# STM32_2024-08-02.net
KiCad netlist of a schematic drawn in EasyEDA Pro
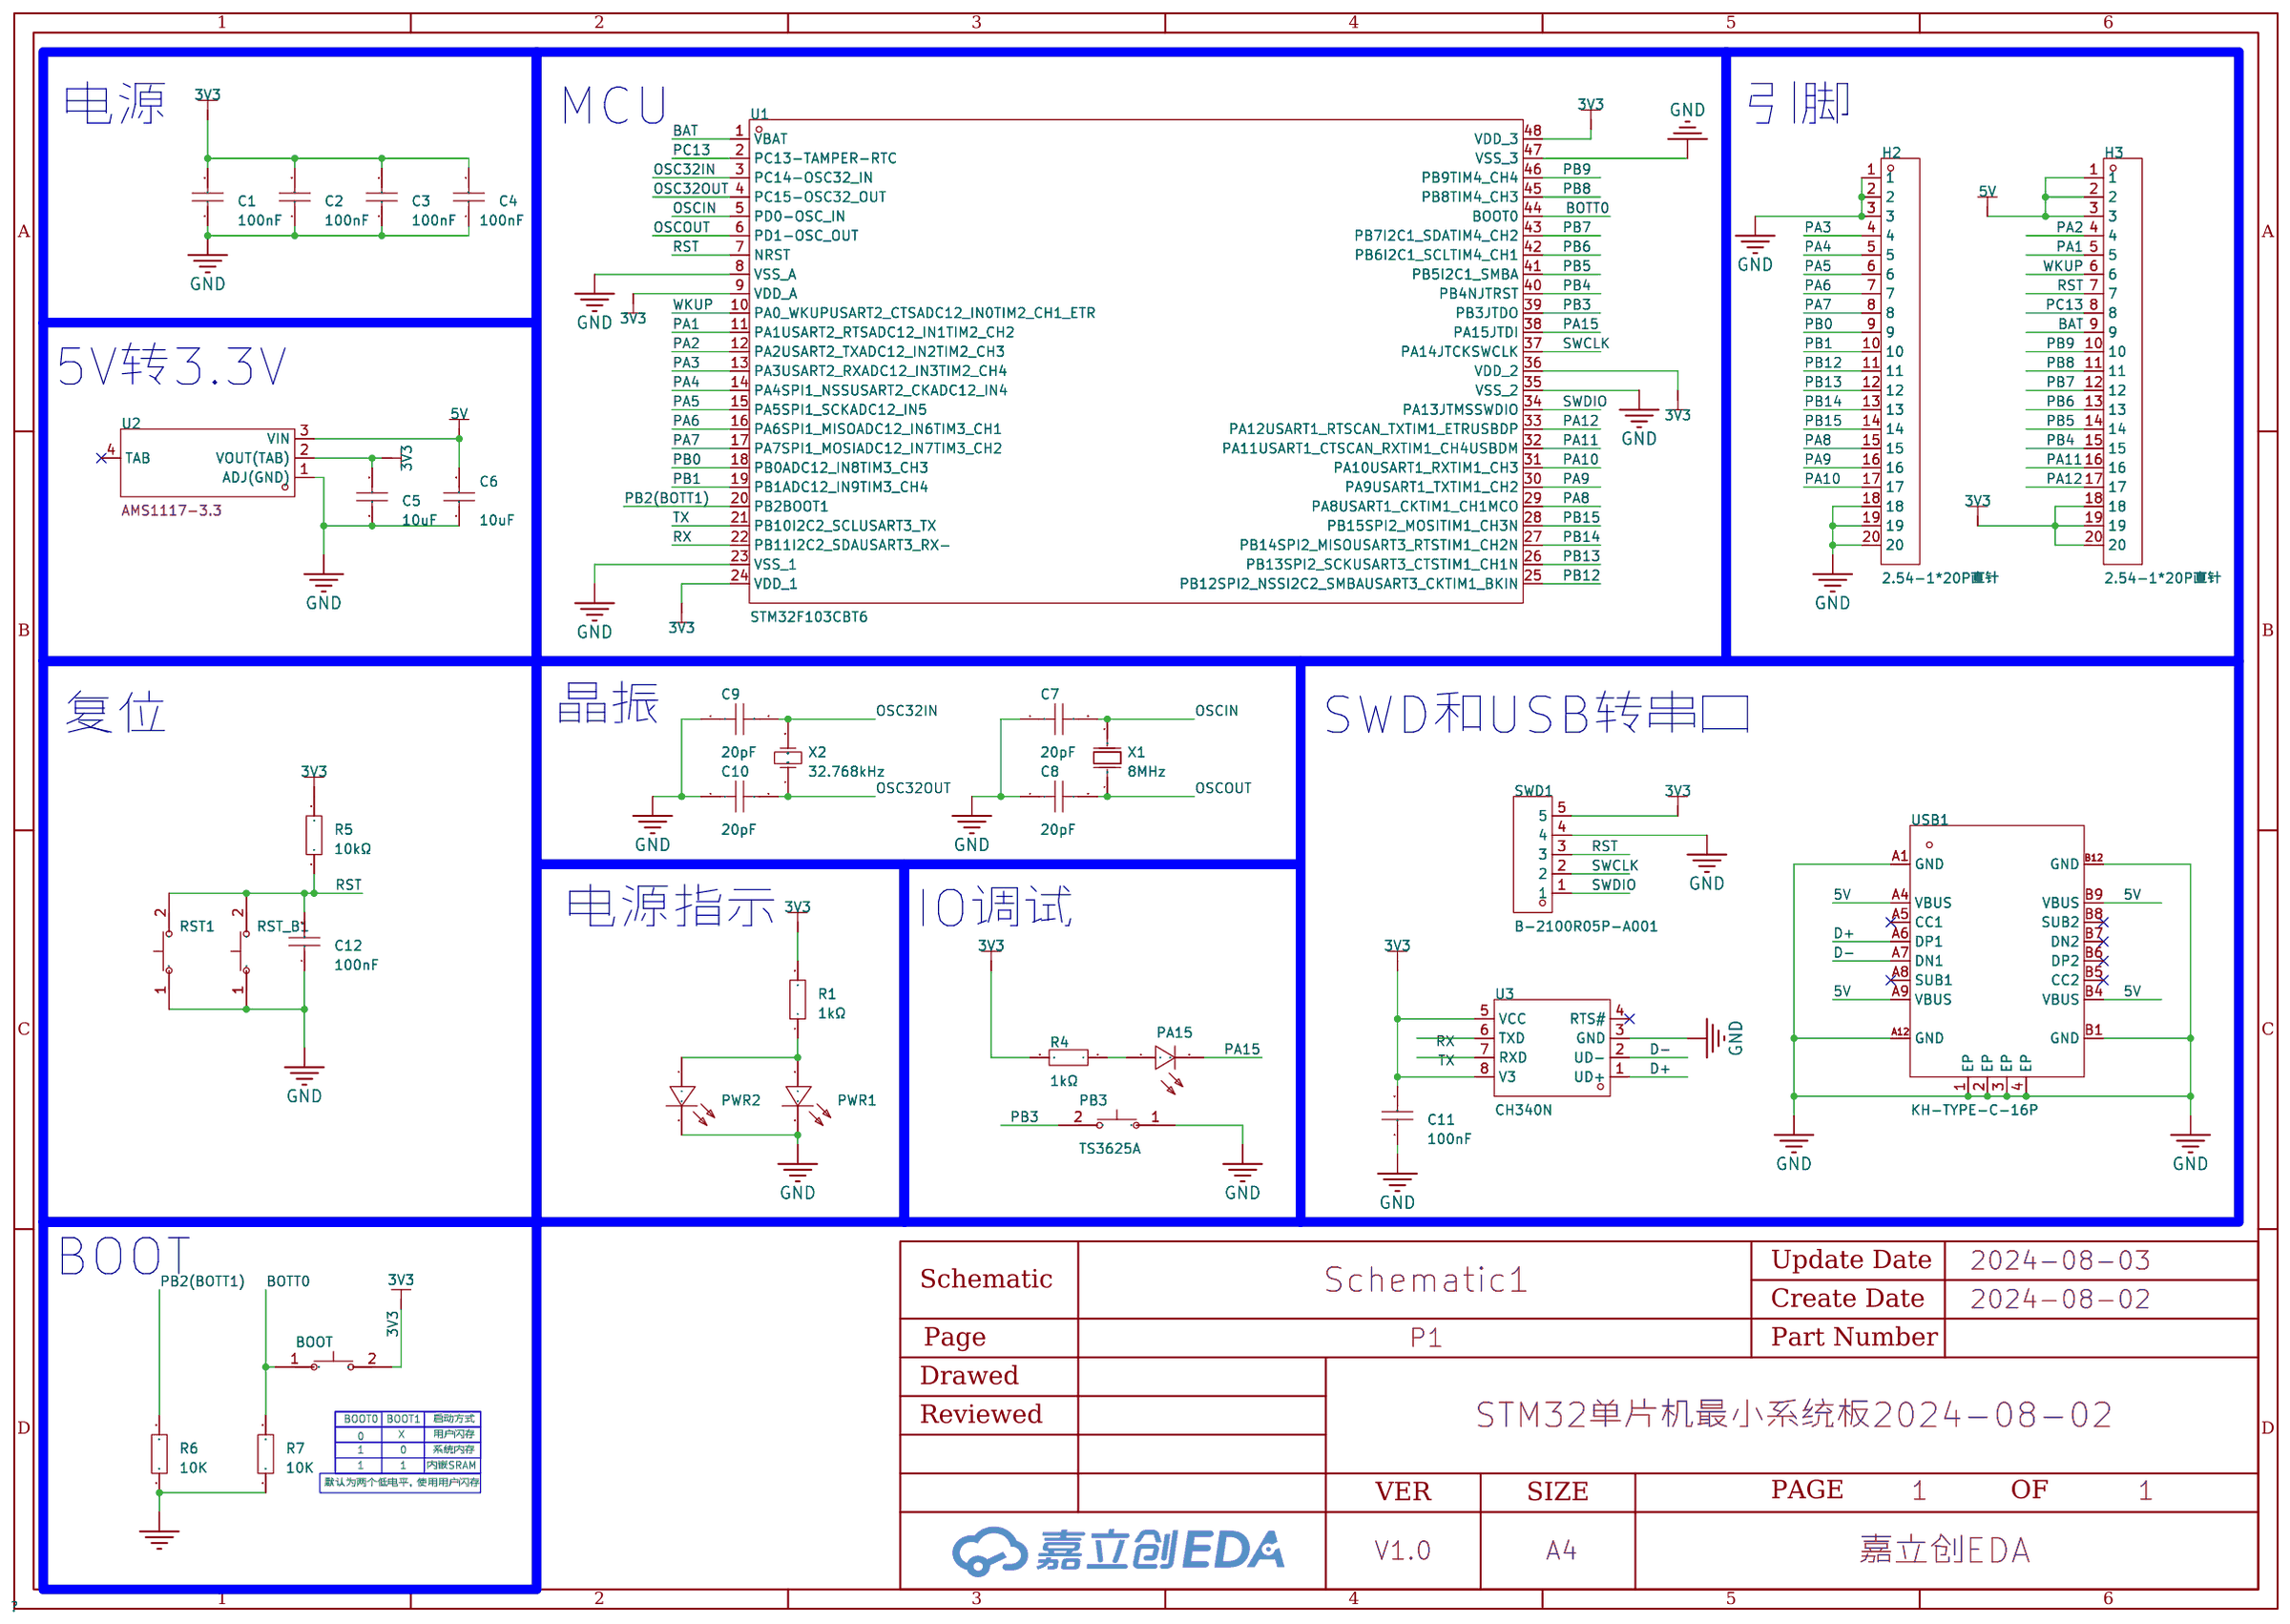
[diagram p0: schematic sheet]

(export (version "E")
  (design (tool "Eeschema 10.0.6"))
  (components
    (comp (ref "BOOT")
      (value "TS3625A")
      (footprint "easyedapro:KEY-SMD_L6.0-W3.5-LS8.4")
      (fields (field (name "Manufacturer") "SHOU HAN(首韩)"))
      (libsource (lib "easyedapro") (part "TS3625A"))
    )
    (comp (ref "C1")
      (value "100nF")
      (footprint "easyedapro:C0805")
      (description "温度系数:X7R;容值:100nF;精度:±10%;额定电压:50V;")
      (fields (field (name "Manufacturer Part") "0805B104K500NT") (field (name "Manufacturer") "FH(风华)"))
      (libsource (lib "easyedapro") (part "0805B104K500NT"))
    )
    (comp (ref "C2")
      (value "100nF")
      (footprint "easyedapro:C0805")
      (description "温度系数:X7R;容值:100nF;精度:±10%;额定电压:50V;")
      (fields (field (name "Manufacturer Part") "0805B104K500NT") (field (name "Manufacturer") "FH(风华)"))
      (libsource (lib "easyedapro") (part "0805B104K500NT"))
    )
    (comp (ref "C3")
      (value "100nF")
      (footprint "easyedapro:C0805")
      (description "温度系数:X7R;容值:100nF;精度:±10%;额定电压:50V;")
      (fields (field (name "Manufacturer Part") "0805B104K500NT") (field (name "Manufacturer") "FH(风华)"))
      (libsource (lib "easyedapro") (part "0805B104K500NT"))
    )
    (comp (ref "C4")
      (value "100nF")
      (footprint "easyedapro:C0805")
      (description "温度系数:X7R;容值:100nF;精度:±10%;额定电压:50V;")
      (fields (field (name "Manufacturer Part") "0805B104K500NT") (field (name "Manufacturer") "FH(风华)"))
      (libsource (lib "easyedapro") (part "0805B104K500NT"))
    )
    (comp (ref "C5")
      (value "10uF")
      (footprint "easyedapro:C0805")
      (description "容值:10uF;精度:±10%;额定电压:25V;材质(温度系数):X5R;")
      (fields (field (name "Manufacturer Part") "0805X106K250NT") (field (name "Manufacturer") "FH(风华)"))
      (libsource (lib "easyedapro") (part "0805X106K250NT"))
    )
    (comp (ref "C6")
      (value "10uF")
      (footprint "easyedapro:C0805")
      (description "容值:10uF;精度:±10%;额定电压:25V;材质(温度系数):X5R;")
      (fields (field (name "Manufacturer Part") "0805X106K250NT") (field (name "Manufacturer") "FH(风华)"))
      (libsource (lib "easyedapro") (part "0805X106K250NT"))
    )
    (comp (ref "C7")
      (value "20pF")
      (footprint "easyedapro:C0805")
      (description "容值:20pF;精度:±5%;额定电压:50V;材质(温度系数):C0G;")
      (fields (field (name "Manufacturer Part") "0805CG200J500NT") (field (name "Manufacturer") "FH(风华)"))
      (libsource (lib "easyedapro") (part "0805CG200J500NT"))
    )
    (comp (ref "C8")
      (value "20pF")
      (footprint "easyedapro:C0805")
      (description "容值:20pF;精度:±5%;额定电压:50V;材质(温度系数):C0G;")
      (fields (field (name "Manufacturer Part") "0805CG200J500NT") (field (name "Manufacturer") "FH(风华)"))
      (libsource (lib "easyedapro") (part "0805CG200J500NT"))
    )
    (comp (ref "C9")
      (value "20pF")
      (footprint "easyedapro:C0805")
      (description "容值:20pF;精度:±5%;额定电压:50V;材质(温度系数):C0G;")
      (fields (field (name "Manufacturer Part") "0805CG200J500NT") (field (name "Manufacturer") "FH(风华)"))
      (libsource (lib "easyedapro") (part "0805CG200J500NT"))
    )
    (comp (ref "C10")
      (value "20pF")
      (footprint "easyedapro:C0805")
      (description "容值:20pF;精度:±5%;额定电压:50V;材质(温度系数):C0G;")
      (fields (field (name "Manufacturer Part") "0805CG200J500NT") (field (name "Manufacturer") "FH(风华)"))
      (libsource (lib "easyedapro") (part "0805CG200J500NT"))
    )
    (comp (ref "C11")
      (value "100nF")
      (footprint "easyedapro:C0805")
      (description "温度系数:X7R;容值:100nF;精度:±10%;额定电压:50V;")
      (fields (field (name "Manufacturer Part") "0805B104K500NT") (field (name "Manufacturer") "FH(风华)"))
      (libsource (lib "easyedapro") (part "0805B104K500NT"))
    )
    (comp (ref "C12")
      (value "100nF")
      (footprint "easyedapro:C0805")
      (description "温度系数:X7R;容值:100nF;精度:±10%;额定电压:50V;")
      (fields (field (name "Manufacturer Part") "0805B104K500NT") (field (name "Manufacturer") "FH(风华)"))
      (libsource (lib "easyedapro") (part "0805B104K500NT"))
    )
    (comp (ref "H2")
      (value "2.54-1*20P直针")
      (footprint "easyedapro:HDR-TH_20P-P2.54-V-M-1")
      (fields (field (name "Manufacturer") "BOOMELE(博穆精密)"))
      (libsource (lib "easyedapro") (part "Header-Male-2.54_1x20"))
    )
    (comp (ref "H3")
      (value "2.54-1*20P直针")
      (footprint "easyedapro:HDR-TH_20P-P2.54-V-M-1")
      (fields (field (name "Manufacturer") "BOOMELE(博穆精密)"))
      (libsource (lib "easyedapro") (part "Header-Male-2.54_1x20"))
    )
    (comp (ref "PA15")
      (value "NCD0805G1")
      (footprint "easyedapro:LED0805-R-RD")
      (description "发光颜色:翠绿;")
      (fields (field (name "Manufacturer") "国星光电"))
      (libsource (lib "easyedapro") (part "17-21SURC/S530-A3/TR8"))
    )
    (comp (ref "PB3")
      (value "TS3625A")
      (footprint "easyedapro:KEY-SMD_L6.0-W3.5-LS8.4")
      (fields (field (name "Manufacturer") "SHOU HAN(首韩)"))
      (libsource (lib "easyedapro") (part "TS3625A"))
    )
    (comp (ref "PWR1")
      (value "NCD0805G1")
      (footprint "easyedapro:LED0805-R-RD")
      (description "照明颜色:翠绿;色温 - CCT（K）:-;主波长/色坐标:525~537.5nm;")
      (fields (field (name "Manufacturer") "国星光电"))
      (libsource (lib "easyedapro") (part "FC-2012UGK-520D5"))
    )
    (comp (ref "PWR2")
      (value "NCD0805G1")
      (footprint "easyedapro:LED0805-R-RD")
      (description "照明颜色:翠绿;色温 - CCT（K）:-;主波长/色坐标:525~537.5nm;")
      (fields (field (name "Manufacturer") "国星光电"))
      (libsource (lib "easyedapro") (part "FC-2012UGK-520D5"))
    )
    (comp (ref "R1")
      (value "1kΩ")
      (footprint "easyedapro:R0805")
      (description "精度:±1%;功率:125mW;电阻类型:厚膜电阻;最大工作电压:150V;温度系数:±100ppm/°C;工作温度范围:-55°C~+155°C;阻值:1kΩ;")
      (fields
        (field (name "Manufacturer Part") "0805W8F1001T5E")
        (field (name "Manufacturer") "UNI-ROYAL(厚声)")
      )
      (libsource (lib "easyedapro") (part "0805W8F1001T5E"))
    )
    (comp (ref "R4")
      (value "1kΩ")
      (footprint "easyedapro:R0805")
      (description "精度:±1%;功率:125mW;电阻类型:厚膜电阻;最大工作电压:150V;温度系数:±100ppm/°C;工作温度范围:-55°C~+155°C;阻值:1kΩ;")
      (fields
        (field (name "Manufacturer Part") "0805W8F1001T5E")
        (field (name "Manufacturer") "UNI-ROYAL(厚声)")
      )
      (libsource (lib "easyedapro") (part "0805W8F1001T5E"))
    )
    (comp (ref "R5")
      (value "10kΩ")
      (footprint "easyedapro:R0805")
      (description "精度:±1%;温度系数:±100ppm/°C;阻值:10kΩ;功率:1/8W;最大工作电压:150V;工作温度范围:-55°C~+155°C;")
      (fields
        (field (name "Manufacturer Part") "0805W8F1002T5E")
        (field (name "Manufacturer") "UNI-ROYAL(厚声)")
      )
      (libsource (lib "easyedapro") (part "0805W8F1002T5E"))
    )
    (comp (ref "R6") (value "10K") (footprint "easyedapro:R0603") (libsource (lib "easyedapro") (part "电阻")))
    (comp (ref "R7") (value "10K") (footprint "easyedapro:R0603") (libsource (lib "easyedapro") (part "电阻")))
    (comp (ref "RST1")
      (value "TS3625A")
      (footprint "easyedapro:KEY-SMD_L6.0-W3.5-LS8.4")
      (fields (field (name "Manufacturer") "SHOU HAN(首韩)"))
      (libsource (lib "easyedapro") (part "TS3625A"))
    )
    (comp (ref "RST_B1")
      (value "TS3625A")
      (footprint "easyedapro:KEY-SMD_L6.0-W3.5-LS8.4")
      (fields (field (name "Manufacturer") "SHOU HAN(首韩)"))
      (libsource (lib "easyedapro") (part "TS3625A"))
    )
    (comp (ref "SWD1")
      (value "B-2100R05P-A001")
      (footprint "easyedapro:HDR-TH_5P-P2.54-H-M-W10.4")
      (fields (field (name "Manufacturer") "Ckmtw(灿科盟)"))
      (libsource (lib "easyedapro") (part "PZ254R-11-05P"))
    )
    (comp (ref "U1")
      (value "STM32F103CBT6")
      (footprint "easyedapro:LQFP-48_L7.0-W7.0-P0.50-LS9.0-BL")
      (description "工作电压:2V ~ 3.6V;主频（MAX):72MHz;")
      (fields (field (name "Manufacturer") "ST(意法半导体)"))
      (libsource (lib "easyedapro") (part "STM32F103CBT6"))
    )
    (comp (ref "U2")
      (value "AMS1117-3.3")
      (footprint "easyedapro:SOT-223-4_L6.5-W3.5-P2.30-LS7.0-BR")
      (description "输出类型:固定;输出极性:正;最大输入电压:18V;输出电压:3.3V;输出电流:1A;电源纹波抑制比(PSRR):60dB@(120Hz);")
      (fields (field (name "Manufacturer Part") "AMS1117-3.3") (field (name "Manufacturer") "AMS"))
      (libsource (lib "easyedapro") (part "AMS1117-3.3_C347222"))
    )
    (comp (ref "U3")
      (value "CH340N")
      (footprint "easyedapro:SOP-8_L4.9-W3.9-P1.27-LS6.0-BL")
      (fields (field (name "Manufacturer") "WCH(南京沁恒)"))
      (libsource (lib "easyedapro") (part "CH340N_C2977777"))
    )
    (comp (ref "USB1")
      (value "KH-TYPE-C-16P")
      (footprint "easyedapro:USB-C-SMD_KH-TYPE-C-16P")
      (description "连接器类型:Type-C;标准:-;公母:母座;触点数量:16;端口数量:1;安装方式:卧贴;额定电流 - 电源:3A;工作温度范围:-40°C~+85°C;")
      (fields (field (name "Manufacturer") "kinghelm(金航标)"))
      (libsource (lib "easyedapro") (part "KH-TYPE-C-16P"))
    )
    (comp (ref "X1")
      (value "8MHz")
      (footprint "easyedapro:OSC-SMD_L5.0-W3.2")
      (description "晶振类型:贴片无源晶振;频率:8MHz;频率公差:±10ppm;频率稳定度:±50ppm;负载电容:20pF;工作温度:-40°C~+85°C;")
      (fields (field (name "Manufacturer Part") "X32258MOB4SI") (field (name "Manufacturer") "YXC(扬兴晶振)"))
      (libsource (lib "easyedapro") (part "X50328MSB2GI"))
    )
    (comp (ref "X2")
      (value "32.768kHz")
      (footprint "easyedapro:OSC-TH_BD2.0-P0.70-D0.3")
      (description "晶振类型:圆柱体晶振;频率:32.768kHz;频率公差:±10ppm;负载电容:12.5pF;工作温度:-20°C~+70°C;")
      (fields (field (name "Manufacturer Part") "Q13FC1350000400") (field (name "Manufacturer") "EPSON(爱普生)"))
      (libsource (lib "easyedapro") (part "X206032768KGB2SC"))
    )
  )
  (nets
    (net (code "1") (name "/BAT") (class "Default")
      (node (ref "H3") (pin "9") (pinfunction "9_9") (pintype "input"))
      (node (ref "U1") (pin "1") (pinfunction "VBAT_1") (pintype "input"))
    )
    (net (code "2") (name "/BOTT0") (class "Default")
      (node (ref "BOOT") (pin "1") (pinfunction "1_1") (pintype "input"))
      (node (ref "R7") (pin "2") (pinfunction "2_2") (pintype "input"))
      (node (ref "U1") (pin "44") (pinfunction "BOOT0_44") (pintype "input"))
    )
    (net (code "3") (name "/D+") (class "Default")
      (node (ref "U3") (pin "1") (pinfunction "UD+_1") (pintype "input"))
      (node (ref "USB1") (pin "A6") (pinfunction "DP1_A6") (pintype "input"))
    )
    (net (code "4") (name "/D-") (class "Default")
      (node (ref "U3") (pin "2") (pinfunction "UD-_2") (pintype "input"))
      (node (ref "USB1") (pin "A7") (pinfunction "DN1_A7") (pintype "input"))
    )
    (net (code "5") (name "/OSC32IN") (class "Default")
      (node (ref "C9") (pin "2") (pinfunction "2_2") (pintype "input"))
      (node (ref "U1") (pin "3") (pinfunction "PC14-OSC32_IN_3") (pintype "input"))
      (node (ref "X2") (pin "2") (pinfunction "OSC2_2") (pintype "input"))
    )
    (net (code "6") (name "/OSC32OUT") (class "Default")
      (node (ref "C10") (pin "2") (pinfunction "2_2") (pintype "input"))
      (node (ref "U1") (pin "4") (pinfunction "PC15-OSC32_OUT_4") (pintype "input"))
      (node (ref "X2") (pin "1") (pinfunction "OSC1_1") (pintype "input"))
    )
    (net (code "7") (name "/OSCIN") (class "Default")
      (node (ref "C7") (pin "2") (pinfunction "2_2") (pintype "input"))
      (node (ref "U1") (pin "5") (pinfunction "PD0-OSC_IN_5") (pintype "input"))
      (node (ref "X1") (pin "2") (pinfunction "OSC2_2") (pintype "input"))
    )
    (net (code "8") (name "/OSCOUT") (class "Default")
      (node (ref "C8") (pin "2") (pinfunction "2_2") (pintype "input"))
      (node (ref "U1") (pin "6") (pinfunction "PD1-OSC_OUT_6") (pintype "input"))
      (node (ref "X1") (pin "1") (pinfunction "OSC1_1") (pintype "input"))
    )
    (net (code "9") (name "/PA1") (class "Default")
      (node (ref "H3") (pin "5") (pinfunction "5_5") (pintype "input"))
      (node (ref "U1") (pin "11") (pinfunction "PA1USART2_RTSADC12_IN1TIM2_CH2_11") (pintype "input"))
    )
    (net (code "10") (name "/PA2") (class "Default")
      (node (ref "H3") (pin "4") (pinfunction "4_4") (pintype "input"))
      (node (ref "U1") (pin "12") (pinfunction "PA2USART2_TXADC12_IN2TIM2_CH3_12") (pintype "input"))
    )
    (net (code "11") (name "/PA3") (class "Default")
      (node (ref "H2") (pin "4") (pinfunction "4_4") (pintype "input"))
      (node (ref "U1") (pin "13") (pinfunction "PA3USART2_RXADC12_IN3TIM2_CH4_13") (pintype "input"))
    )
    (net (code "12") (name "/PA4") (class "Default")
      (node (ref "H2") (pin "5") (pinfunction "5_5") (pintype "input"))
      (node (ref "U1") (pin "14") (pinfunction "PA4SPI1_NSSUSART2_CKADC12_IN4_14") (pintype "input"))
    )
    (net (code "13") (name "/PA5") (class "Default")
      (node (ref "H2") (pin "6") (pinfunction "6_6") (pintype "input"))
      (node (ref "U1") (pin "15") (pinfunction "PA5SPI1_SCKADC12_IN5_15") (pintype "input"))
    )
    (net (code "14") (name "/PA6") (class "Default")
      (node (ref "H2") (pin "7") (pinfunction "7_7") (pintype "input"))
      (node (ref "U1") (pin "16") (pinfunction "PA6SPI1_MISOADC12_IN6TIM3_CH1_16") (pintype "input"))
    )
    (net (code "15") (name "/PA7") (class "Default")
      (node (ref "H2") (pin "8") (pinfunction "8_8") (pintype "input"))
      (node (ref "U1") (pin "17") (pinfunction "PA7SPI1_MOSIADC12_IN7TIM3_CH2_17") (pintype "input"))
    )
    (net (code "16") (name "/PA8") (class "Default")
      (node (ref "H2") (pin "15") (pinfunction "15_15") (pintype "input"))
      (node (ref "U1") (pin "29") (pinfunction "PA8USART1_CKTIM1_CH1MCO_29") (pintype "input"))
    )
    (net (code "17") (name "/PA9") (class "Default")
      (node (ref "H2") (pin "16") (pinfunction "16_16") (pintype "input"))
      (node (ref "U1") (pin "30") (pinfunction "PA9USART1_TXTIM1_CH2_30") (pintype "input"))
    )
    (net (code "18") (name "/PA10") (class "Default")
      (node (ref "H2") (pin "17") (pinfunction "17_17") (pintype "input"))
      (node (ref "U1") (pin "31") (pinfunction "PA10USART1_RXTIM1_CH3_31") (pintype "input"))
    )
    (net (code "19") (name "/PA11") (class "Default")
      (node (ref "H3") (pin "16") (pinfunction "16_16") (pintype "input"))
      (node (ref "U1") (pin "32") (pinfunction "PA11USART1_CTSCAN_RXTIM1_CH4USBDM_32") (pintype "input"))
    )
    (net (code "20") (name "/PA12") (class "Default")
      (node (ref "H3") (pin "17") (pinfunction "17_17") (pintype "input"))
      (node (ref "U1") (pin "33") (pinfunction "PA12USART1_RTSCAN_TXTIM1_ETRUSBDP_33") (pintype "input"))
    )
    (net (code "21") (name "/PA15") (class "Default")
      (node (ref "PA15") (pin "2") (pinfunction "C_2") (pintype "input"))
      (node (ref "U1") (pin "38") (pinfunction "PA15JTDI_38") (pintype "input"))
    )
    (net (code "22") (name "/PB0") (class "Default")
      (node (ref "H2") (pin "9") (pinfunction "9_9") (pintype "input"))
      (node (ref "U1") (pin "18") (pinfunction "PB0ADC12_IN8TIM3_CH3_18") (pintype "input"))
    )
    (net (code "23") (name "/PB1") (class "Default")
      (node (ref "H2") (pin "10") (pinfunction "10_10") (pintype "input"))
      (node (ref "U1") (pin "19") (pinfunction "PB1ADC12_IN9TIM3_CH4_19") (pintype "input"))
    )
    (net (code "24") (name "/PB2(BOTT1)") (class "Default")
      (node (ref "R6") (pin "2") (pinfunction "2_2") (pintype "input"))
      (node (ref "U1") (pin "20") (pinfunction "PB2BOOT1_20") (pintype "input"))
    )
    (net (code "25") (name "/PB3") (class "Default")
      (node (ref "PB3") (pin "2") (pinfunction "2_2") (pintype "input"))
      (node (ref "U1") (pin "39") (pinfunction "PB3JTDO_39") (pintype "input"))
    )
    (net (code "26") (name "/PB4") (class "Default")
      (node (ref "H3") (pin "15") (pinfunction "15_15") (pintype "input"))
      (node (ref "U1") (pin "40") (pinfunction "PB4NJTRST_40") (pintype "input"))
    )
    (net (code "27") (name "/PB5") (class "Default")
      (node (ref "H3") (pin "14") (pinfunction "14_14") (pintype "input"))
      (node (ref "U1") (pin "41") (pinfunction "PB5I2C1_SMBA_41") (pintype "input"))
    )
    (net (code "28") (name "/PB6") (class "Default")
      (node (ref "H3") (pin "13") (pinfunction "13_13") (pintype "input"))
      (node (ref "U1") (pin "42") (pinfunction "PB6I2C1_SCLTIM4_CH1_42") (pintype "input"))
    )
    (net (code "29") (name "/PB7") (class "Default")
      (node (ref "H3") (pin "12") (pinfunction "12_12") (pintype "input"))
      (node (ref "U1") (pin "43") (pinfunction "PB7I2C1_SDATIM4_CH2_43") (pintype "input"))
    )
    (net (code "30") (name "/PB8") (class "Default")
      (node (ref "H3") (pin "11") (pinfunction "11_11") (pintype "input"))
      (node (ref "U1") (pin "45") (pinfunction "PB8TIM4_CH3_45") (pintype "input"))
    )
    (net (code "31") (name "/PB9") (class "Default")
      (node (ref "H3") (pin "10") (pinfunction "10_10") (pintype "input"))
      (node (ref "U1") (pin "46") (pinfunction "PB9TIM4_CH4_46") (pintype "input"))
    )
    (net (code "32") (name "/PB12") (class "Default")
      (node (ref "H2") (pin "11") (pinfunction "11_11") (pintype "input"))
      (node (ref "U1") (pin "25") (pinfunction "PB12SPI2_NSSI2C2_SMBAUSART3_CKTIM1_BKIN_25") (pintype "input"))
    )
    (net (code "33") (name "/PB13") (class "Default")
      (node (ref "H2") (pin "12") (pinfunction "12_12") (pintype "input"))
      (node (ref "U1") (pin "26") (pinfunction "PB13SPI2_SCKUSART3_CTSTIM1_CH1N_26") (pintype "input"))
    )
    (net (code "34") (name "/PB14") (class "Default")
      (node (ref "H2") (pin "13") (pinfunction "13_13") (pintype "input"))
      (node (ref "U1") (pin "27") (pinfunction "PB14SPI2_MISOUSART3_RTSTIM1_CH2N_27") (pintype "input"))
    )
    (net (code "35") (name "/PB15") (class "Default")
      (node (ref "H2") (pin "14") (pinfunction "14_14") (pintype "input"))
      (node (ref "U1") (pin "28") (pinfunction "PB15SPI2_MOSITIM1_CH3N_28") (pintype "input"))
    )
    (net (code "36") (name "/PC13") (class "Default")
      (node (ref "H3") (pin "8") (pinfunction "8_8") (pintype "input"))
      (node (ref "U1") (pin "2") (pinfunction "PC13-TAMPER-RTC_2") (pintype "input"))
    )
    (net (code "37") (name "/RST") (class "Default")
      (node (ref "C12") (pin "2") (pinfunction "2_2") (pintype "input"))
      (node (ref "H3") (pin "7") (pinfunction "7_7") (pintype "input"))
      (node (ref "R5") (pin "1") (pinfunction "1_1") (pintype "input"))
      (node (ref "RST1") (pin "2") (pinfunction "2_2") (pintype "input"))
      (node (ref "RST_B1") (pin "2") (pinfunction "2_2") (pintype "input"))
      (node (ref "SWD1") (pin "3") (pinfunction "3_3") (pintype "input"))
      (node (ref "U1") (pin "7") (pinfunction "NRST_7") (pintype "input"))
    )
    (net (code "38") (name "/RX") (class "Default")
      (node (ref "U1") (pin "22") (pinfunction "PB11I2C2_SDAUSART3_RX-_22") (pintype "input"))
      (node (ref "U3") (pin "6") (pinfunction "TXD_6") (pintype "input"))
    )
    (net (code "39") (name "/SWCLK") (class "Default")
      (node (ref "SWD1") (pin "2") (pinfunction "2_2") (pintype "input"))
      (node (ref "U1") (pin "37") (pinfunction "PA14JTCKSWCLK_37") (pintype "input"))
    )
    (net (code "40") (name "/SWDIO") (class "Default")
      (node (ref "SWD1") (pin "1") (pinfunction "1_1") (pintype "input"))
      (node (ref "U1") (pin "34") (pinfunction "PA13JTMSSWDIO_34") (pintype "input"))
    )
    (net (code "41") (name "/TX") (class "Default")
      (node (ref "U1") (pin "21") (pinfunction "PB10I2C2_SCLUSART3_TX_21") (pintype "input"))
      (node (ref "U3") (pin "7") (pinfunction "RXD_7") (pintype "input"))
    )
    (net (code "42") (name "/WKUP") (class "Default")
      (node (ref "H3") (pin "6") (pinfunction "6_6") (pintype "input"))
      (node (ref "U1") (pin "10") (pinfunction "PA0_WKUPUSART2_CTSADC12_IN0TIM2_CH1_ETR_10") (pintype "input"))
    )
    (net (code "43") (name "3V3") (class "Default")
      (node (ref "BOOT") (pin "2") (pinfunction "2_2") (pintype "input"))
      (node (ref "C1") (pin "2") (pinfunction "2_2") (pintype "input"))
      (node (ref "C11") (pin "2") (pinfunction "2_2") (pintype "input"))
      (node (ref "C2") (pin "2") (pinfunction "2_2") (pintype "input"))
      (node (ref "C3") (pin "2") (pinfunction "2_2") (pintype "input"))
      (node (ref "C4") (pin "2") (pinfunction "2_2") (pintype "input"))
      (node (ref "C5") (pin "2") (pinfunction "2_2") (pintype "input"))
      (node (ref "H3") (pin "18") (pinfunction "18_18") (pintype "input"))
      (node (ref "H3") (pin "19") (pinfunction "19_19") (pintype "input"))
      (node (ref "H3") (pin "20") (pinfunction "20_20") (pintype "input"))
      (node (ref "R1") (pin "2") (pinfunction "2_2") (pintype "input"))
      (node (ref "R4") (pin "2") (pinfunction "2_2") (pintype "input"))
      (node (ref "R5") (pin "2") (pinfunction "2_2") (pintype "input"))
      (node (ref "SWD1") (pin "5") (pinfunction "5_5") (pintype "input"))
      (node (ref "U1") (pin "24") (pinfunction "VDD_1_24") (pintype "input"))
      (node (ref "U1") (pin "36") (pinfunction "VDD_2_36") (pintype "input"))
      (node (ref "U1") (pin "48") (pinfunction "VDD_3_48") (pintype "input"))
      (node (ref "U1") (pin "9") (pinfunction "VDD_A_9") (pintype "input"))
      (node (ref "U2") (pin "2") (pinfunction "VOUT(TAB)_2") (pintype "input"))
      (node (ref "U3") (pin "5") (pinfunction "VCC_5") (pintype "input"))
      (node (ref "U3") (pin "8") (pinfunction "V3_8") (pintype "input"))
    )
    (net (code "44") (name "5V") (class "Default")
      (node (ref "C6") (pin "2") (pinfunction "2_2") (pintype "input"))
      (node (ref "H3") (pin "1") (pinfunction "1_1") (pintype "input"))
      (node (ref "H3") (pin "2") (pinfunction "2_2") (pintype "input"))
      (node (ref "H3") (pin "3") (pinfunction "3_3") (pintype "input"))
      (node (ref "U2") (pin "3") (pinfunction "VIN_3") (pintype "input"))
      (node (ref "USB1") (pin "A4") (pinfunction "VBUS_A4") (pintype "input"))
      (node (ref "USB1") (pin "A9") (pinfunction "VBUS_A9") (pintype "input"))
      (node (ref "USB1") (pin "B4") (pinfunction "VBUS_B4") (pintype "input"))
      (node (ref "USB1") (pin "B9") (pinfunction "VBUS_B9") (pintype "input"))
    )
    (net (code "45") (name "GND") (class "Default")
      (node (ref "C1") (pin "1") (pinfunction "1_1") (pintype "input"))
      (node (ref "C10") (pin "1") (pinfunction "1_1") (pintype "input"))
      (node (ref "C11") (pin "1") (pinfunction "1_1") (pintype "input"))
      (node (ref "C12") (pin "1") (pinfunction "1_1") (pintype "input"))
      (node (ref "C2") (pin "1") (pinfunction "1_1") (pintype "input"))
      (node (ref "C3") (pin "1") (pinfunction "1_1") (pintype "input"))
      (node (ref "C4") (pin "1") (pinfunction "1_1") (pintype "input"))
      (node (ref "C5") (pin "1") (pinfunction "1_1") (pintype "input"))
      (node (ref "C6") (pin "1") (pinfunction "1_1") (pintype "input"))
      (node (ref "C7") (pin "1") (pinfunction "1_1") (pintype "input"))
      (node (ref "C8") (pin "1") (pinfunction "1_1") (pintype "input"))
      (node (ref "C9") (pin "1") (pinfunction "1_1") (pintype "input"))
      (node (ref "H2") (pin "1") (pinfunction "1_1") (pintype "input"))
      (node (ref "H2") (pin "18") (pinfunction "18_18") (pintype "input"))
      (node (ref "H2") (pin "19") (pinfunction "19_19") (pintype "input"))
      (node (ref "H2") (pin "2") (pinfunction "2_2") (pintype "input"))
      (node (ref "H2") (pin "20") (pinfunction "20_20") (pintype "input"))
      (node (ref "H2") (pin "3") (pinfunction "3_3") (pintype "input"))
      (node (ref "PB3") (pin "1") (pinfunction "1_1") (pintype "input"))
      (node (ref "PWR1") (pin "2") (pinfunction "K_2") (pintype "input"))
      (node (ref "PWR2") (pin "2") (pinfunction "K_2") (pintype "input"))
      (node (ref "R6") (pin "1") (pinfunction "1_1") (pintype "input"))
      (node (ref "R7") (pin "1") (pinfunction "1_1") (pintype "input"))
      (node (ref "RST1") (pin "1") (pinfunction "1_1") (pintype "input"))
      (node (ref "RST_B1") (pin "1") (pinfunction "1_1") (pintype "input"))
      (node (ref "SWD1") (pin "4") (pinfunction "4_4") (pintype "input"))
      (node (ref "U1") (pin "23") (pinfunction "VSS_1_23") (pintype "input"))
      (node (ref "U1") (pin "35") (pinfunction "VSS_2_35") (pintype "input"))
      (node (ref "U1") (pin "47") (pinfunction "VSS_3_47") (pintype "input"))
      (node (ref "U1") (pin "8") (pinfunction "VSS_A_8") (pintype "input"))
      (node (ref "U2") (pin "1") (pinfunction "ADJ(GND)_1") (pintype "input"))
      (node (ref "U3") (pin "3") (pinfunction "GND_3") (pintype "input"))
      (node (ref "USB1") (pin "1") (pinfunction "EP_1") (pintype "input"))
      (node (ref "USB1") (pin "2") (pinfunction "EP_2") (pintype "input"))
      (node (ref "USB1") (pin "3") (pinfunction "EP_3") (pintype "input"))
      (node (ref "USB1") (pin "4") (pinfunction "EP_4") (pintype "input"))
      (node (ref "USB1") (pin "A1") (pinfunction "GND_A1") (pintype "input"))
      (node (ref "USB1") (pin "A12") (pinfunction "GND_A12") (pintype "input"))
      (node (ref "USB1") (pin "B1") (pinfunction "GND_B1") (pintype "input"))
      (node (ref "USB1") (pin "B12") (pinfunction "GND_B12") (pintype "input"))
    )
    (net (code "46") (name "Net-(PA15-A)") (class "Default")
      (node (ref "PA15") (pin "1") (pinfunction "A_1") (pintype "input"))
      (node (ref "R4") (pin "1") (pinfunction "1_1") (pintype "input"))
    )
    (net (code "47") (name "Net-(PWR1-A)") (class "Default")
      (node (ref "PWR1") (pin "1") (pinfunction "A_1") (pintype "input"))
      (node (ref "PWR2") (pin "1") (pinfunction "A_1") (pintype "input"))
      (node (ref "R1") (pin "1") (pinfunction "1_1") (pintype "input"))
    )
    (net (code "48") (name "unconnected-(U2-TAB-Pad4)") (class "Default")
      (node (ref "U2") (pin "4") (pinfunction "TAB_4") (pintype "input+no_connect"))
    )
    (net (code "49") (name "unconnected-(U3-RTS#-Pad4)") (class "Default")
      (node (ref "U3") (pin "4") (pinfunction "RTS#_4") (pintype "input+no_connect"))
    )
    (net (code "50") (name "unconnected-(USB1-CC1-PadA5)") (class "Default")
      (node (ref "USB1") (pin "A5") (pinfunction "CC1_A5") (pintype "input+no_connect"))
    )
    (net (code "51") (name "unconnected-(USB1-CC2-PadB5)") (class "Default")
      (node (ref "USB1") (pin "B5") (pinfunction "CC2_B5") (pintype "input+no_connect"))
    )
    (net (code "52") (name "unconnected-(USB1-DN2-PadB7)") (class "Default")
      (node (ref "USB1") (pin "B7") (pinfunction "DN2_B7") (pintype "input+no_connect"))
    )
    (net (code "53") (name "unconnected-(USB1-DP2-PadB6)") (class "Default")
      (node (ref "USB1") (pin "B6") (pinfunction "DP2_B6") (pintype "input+no_connect"))
    )
    (net (code "54") (name "unconnected-(USB1-SUB1-PadA8)") (class "Default")
      (node (ref "USB1") (pin "A8") (pinfunction "SUB1_A8") (pintype "input+no_connect"))
    )
    (net (code "55") (name "unconnected-(USB1-SUB2-PadB8)") (class "Default")
      (node (ref "USB1") (pin "B8") (pinfunction "SUB2_B8") (pintype "input+no_connect"))
    )
  )
)
